# EX_Analog.net
KiCad netlist of a schematic drawn in EAGLE
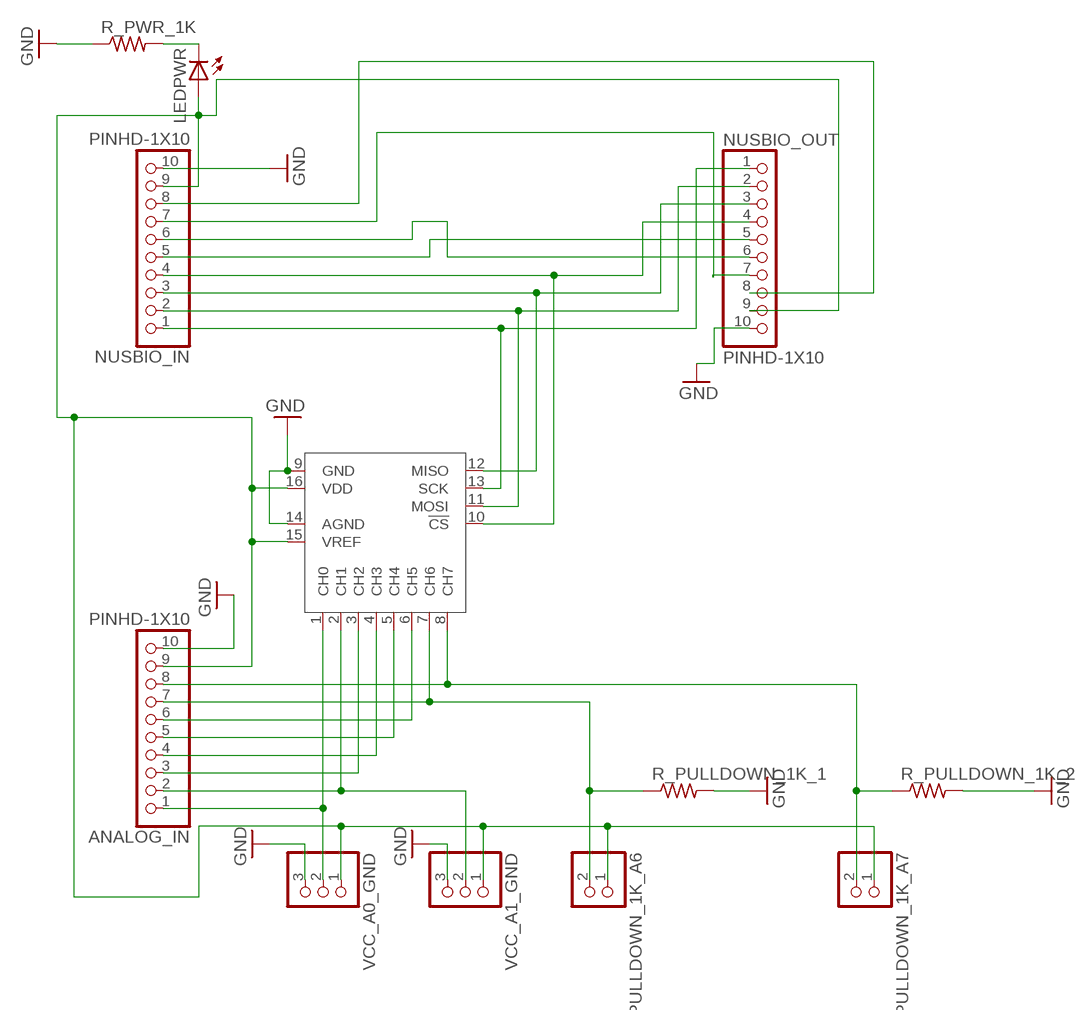
[diagram p0: schematic, sheet 1]

(export (version "E")
  (design (tool "Eeschema 10.0.6"))
  (components
    (comp (ref "ANALOG_IN")
      (value "PINHD-1X10")
      (footprint "eagle-import:1X10-BIG")
      (libsource (lib "eagle-import") (part "PINHD-1X10"))
    )
    (comp (ref "LEDPWR")
      (value "LEDCHIPLED_0805")
      (footprint "eagle-import:CHIPLED_0805")
      (libsource (lib "eagle-import") (part "LEDCHIPLED_0805"))
    )
    (comp (ref "NUSBIO_IN")
      (value "PINHD-1X10")
      (footprint "eagle-import:1X10-BIG")
      (libsource (lib "eagle-import") (part "PINHD-1X10"))
    )
    (comp (ref "NUSBIO_OUT")
      (value "PINHD-1X10")
      (footprint "eagle-import:1X10-BIG")
      (libsource (lib "eagle-import") (part "PINHD-1X10"))
    )
    (comp (ref "PULLDOWN_1K_A6")
      (value "PINHD-1X2")
      (footprint "eagle-import:1X02")
      (libsource (lib "eagle-import") (part "PINHD-1X2"))
    )
    (comp (ref "PULLDOWN_1K_A7")
      (value "PINHD-1X2")
      (footprint "eagle-import:1X02")
      (libsource (lib "eagle-import") (part "PINHD-1X2"))
    )
    (comp (ref "R_PULLDOWN_1K_1")
      (value "R-US_R0805")
      (footprint "eagle-import:R0805")
      (libsource (lib "eagle-import") (part "R-US_R0805"))
    )
    (comp (ref "R_PULLDOWN_1K_2")
      (value "R-US_R0805")
      (footprint "eagle-import:R0805")
      (libsource (lib "eagle-import") (part "R-US_R0805"))
    )
    (comp (ref "R_PWR_1K")
      (value "R-US_R0805")
      (footprint "eagle-import:R0805")
      (libsource (lib "eagle-import") (part "R-US_R0805"))
    )
    (comp (ref "U$1")
      (value "MCP3008SL")
      (footprint "eagle-import:SO16")
      (libsource (lib "eagle-import") (part "MCP3008SL"))
    )
    (comp (ref "VCC_A0_GND")
      (value "PINHD-1X3")
      (footprint "eagle-import:1X03")
      (libsource (lib "eagle-import") (part "PINHD-1X3"))
    )
    (comp (ref "VCC_A1_GND")
      (value "PINHD-1X3")
      (footprint "eagle-import:1X03")
      (libsource (lib "eagle-import") (part "PINHD-1X3"))
    )
  )
  (nets
    (net (code "1") (name "GND") (class "Default")
      (node (ref "ANALOG_IN") (pin "10") (pinfunction "10_10") (pintype "passive"))
      (node (ref "NUSBIO_IN") (pin "10") (pinfunction "10_10") (pintype "passive"))
      (node (ref "NUSBIO_OUT") (pin "10") (pinfunction "10_10") (pintype "passive"))
      (node (ref "R_PULLDOWN_1K_1") (pin "2") (pinfunction "2_2") (pintype "passive"))
      (node (ref "R_PULLDOWN_1K_2") (pin "2") (pinfunction "2_2") (pintype "passive"))
      (node (ref "R_PWR_1K") (pin "1") (pinfunction "1_1") (pintype "passive"))
      (node (ref "U$1") (pin "14") (pinfunction "AGND_14") (pintype "power_in"))
      (node (ref "U$1") (pin "9") (pinfunction "GND_9") (pintype "power_in"))
      (node (ref "VCC_A0_GND") (pin "3") (pinfunction "3_3") (pintype "passive"))
      (node (ref "VCC_A1_GND") (pin "3") (pinfunction "3_3") (pintype "passive"))
    )
    (net (code "2") (name "Net-(LEDPWR-PadC)") (class "Default")
      (node (ref "LEDPWR") (pin "C") (pinfunction "C_C") (pintype "passive"))
      (node (ref "R_PWR_1K") (pin "2") (pinfunction "2_2") (pintype "passive"))
    )
    (net (code "3") (name "Net-(NUSBIO_IN-Pad5)") (class "Default")
      (node (ref "NUSBIO_IN") (pin "5") (pinfunction "5_5") (pintype "passive"))
      (node (ref "NUSBIO_OUT") (pin "5") (pinfunction "5_5") (pintype "passive"))
    )
    (net (code "4") (name "Net-(NUSBIO_IN-Pad6)") (class "Default")
      (node (ref "NUSBIO_IN") (pin "6") (pinfunction "6_6") (pintype "passive"))
      (node (ref "NUSBIO_OUT") (pin "6") (pinfunction "6_6") (pintype "passive"))
    )
    (net (code "5") (name "Net-(NUSBIO_IN-Pad7)") (class "Default")
      (node (ref "NUSBIO_IN") (pin "7") (pinfunction "7_7") (pintype "passive"))
      (node (ref "NUSBIO_OUT") (pin "7") (pinfunction "7_7") (pintype "passive"))
    )
    (net (code "6") (name "Net-(NUSBIO_IN-Pad8)") (class "Default")
      (node (ref "NUSBIO_IN") (pin "8") (pinfunction "8_8") (pintype "passive"))
      (node (ref "NUSBIO_OUT") (pin "8") (pinfunction "8_8") (pintype "passive"))
    )
    (net (code "7") (name "Net-(U$1-CH0)") (class "Default")
      (node (ref "ANALOG_IN") (pin "1") (pinfunction "1_1") (pintype "passive"))
      (node (ref "U$1") (pin "1") (pinfunction "CH0_1") (pintype "input"))
      (node (ref "VCC_A0_GND") (pin "2") (pinfunction "2_2") (pintype "passive"))
    )
    (net (code "8") (name "Net-(U$1-CH1)") (class "Default")
      (node (ref "ANALOG_IN") (pin "2") (pinfunction "2_2") (pintype "passive"))
      (node (ref "U$1") (pin "2") (pinfunction "CH1_2") (pintype "input"))
      (node (ref "VCC_A1_GND") (pin "2") (pinfunction "2_2") (pintype "passive"))
    )
    (net (code "9") (name "Net-(U$1-CH2)") (class "Default")
      (node (ref "ANALOG_IN") (pin "3") (pinfunction "3_3") (pintype "passive"))
      (node (ref "U$1") (pin "3") (pinfunction "CH2_3") (pintype "input"))
    )
    (net (code "10") (name "Net-(U$1-CH3)") (class "Default")
      (node (ref "ANALOG_IN") (pin "4") (pinfunction "4_4") (pintype "passive"))
      (node (ref "U$1") (pin "4") (pinfunction "CH3_4") (pintype "input"))
    )
    (net (code "11") (name "Net-(U$1-CH4)") (class "Default")
      (node (ref "ANALOG_IN") (pin "5") (pinfunction "5_5") (pintype "passive"))
      (node (ref "U$1") (pin "5") (pinfunction "CH4_5") (pintype "input"))
    )
    (net (code "12") (name "Net-(U$1-CH5)") (class "Default")
      (node (ref "ANALOG_IN") (pin "6") (pinfunction "6_6") (pintype "passive"))
      (node (ref "U$1") (pin "6") (pinfunction "CH5_6") (pintype "input"))
    )
    (net (code "13") (name "Net-(U$1-CH6)") (class "Default")
      (node (ref "ANALOG_IN") (pin "7") (pinfunction "7_7") (pintype "passive"))
      (node (ref "PULLDOWN_1K_A6") (pin "2") (pinfunction "2_2") (pintype "passive"))
      (node (ref "R_PULLDOWN_1K_1") (pin "1") (pinfunction "1_1") (pintype "passive"))
      (node (ref "U$1") (pin "7") (pinfunction "CH6_7") (pintype "input"))
    )
    (net (code "14") (name "Net-(U$1-CH7)") (class "Default")
      (node (ref "ANALOG_IN") (pin "8") (pinfunction "8_8") (pintype "passive"))
      (node (ref "PULLDOWN_1K_A7") (pin "2") (pinfunction "2_2") (pintype "passive"))
      (node (ref "R_PULLDOWN_1K_2") (pin "1") (pinfunction "1_1") (pintype "passive"))
      (node (ref "U$1") (pin "8") (pinfunction "CH7_8") (pintype "input"))
    )
    (net (code "15") (name "Net-(U$1-MISO)") (class "Default")
      (node (ref "NUSBIO_IN") (pin "3") (pinfunction "3_3") (pintype "passive"))
      (node (ref "NUSBIO_OUT") (pin "3") (pinfunction "3_3") (pintype "passive"))
      (node (ref "U$1") (pin "12") (pinfunction "MISO_12") (pintype "output"))
    )
    (net (code "16") (name "Net-(U$1-MOSI)") (class "Default")
      (node (ref "NUSBIO_IN") (pin "2") (pinfunction "2_2") (pintype "passive"))
      (node (ref "NUSBIO_OUT") (pin "2") (pinfunction "2_2") (pintype "passive"))
      (node (ref "U$1") (pin "11") (pinfunction "MOSI_11") (pintype "input"))
    )
    (net (code "17") (name "Net-(U$1-SCK)") (class "Default")
      (node (ref "NUSBIO_IN") (pin "1") (pinfunction "1_1") (pintype "passive"))
      (node (ref "NUSBIO_OUT") (pin "1") (pinfunction "1_1") (pintype "passive"))
      (node (ref "U$1") (pin "13") (pinfunction "SCK_13") (pintype "input"))
    )
    (net (code "18") (name "Net-(U$1-VDD)") (class "Default")
      (node (ref "ANALOG_IN") (pin "9") (pinfunction "9_9") (pintype "passive"))
      (node (ref "LEDPWR") (pin "A") (pinfunction "A_A") (pintype "passive"))
      (node (ref "NUSBIO_IN") (pin "9") (pinfunction "9_9") (pintype "passive"))
      (node (ref "NUSBIO_OUT") (pin "9") (pinfunction "9_9") (pintype "passive"))
      (node (ref "PULLDOWN_1K_A6") (pin "1") (pinfunction "1_1") (pintype "passive"))
      (node (ref "PULLDOWN_1K_A7") (pin "1") (pinfunction "1_1") (pintype "passive"))
      (node (ref "U$1") (pin "15") (pinfunction "VREF_15") (pintype "power_in"))
      (node (ref "U$1") (pin "16") (pinfunction "VDD_16") (pintype "power_in"))
      (node (ref "VCC_A0_GND") (pin "1") (pinfunction "1_1") (pintype "passive"))
      (node (ref "VCC_A1_GND") (pin "1") (pinfunction "1_1") (pintype "passive"))
    )
    (net (code "19") (name "Net-(U$1-~{CS})") (class "Default")
      (node (ref "NUSBIO_IN") (pin "4") (pinfunction "4_4") (pintype "passive"))
      (node (ref "NUSBIO_OUT") (pin "4") (pinfunction "4_4") (pintype "passive"))
      (node (ref "U$1") (pin "10") (pinfunction "~{CS}_10") (pintype "input"))
    )
  )
)
